# ASL2001.net
KiCad netlist of a schematic drawn in EAGLE
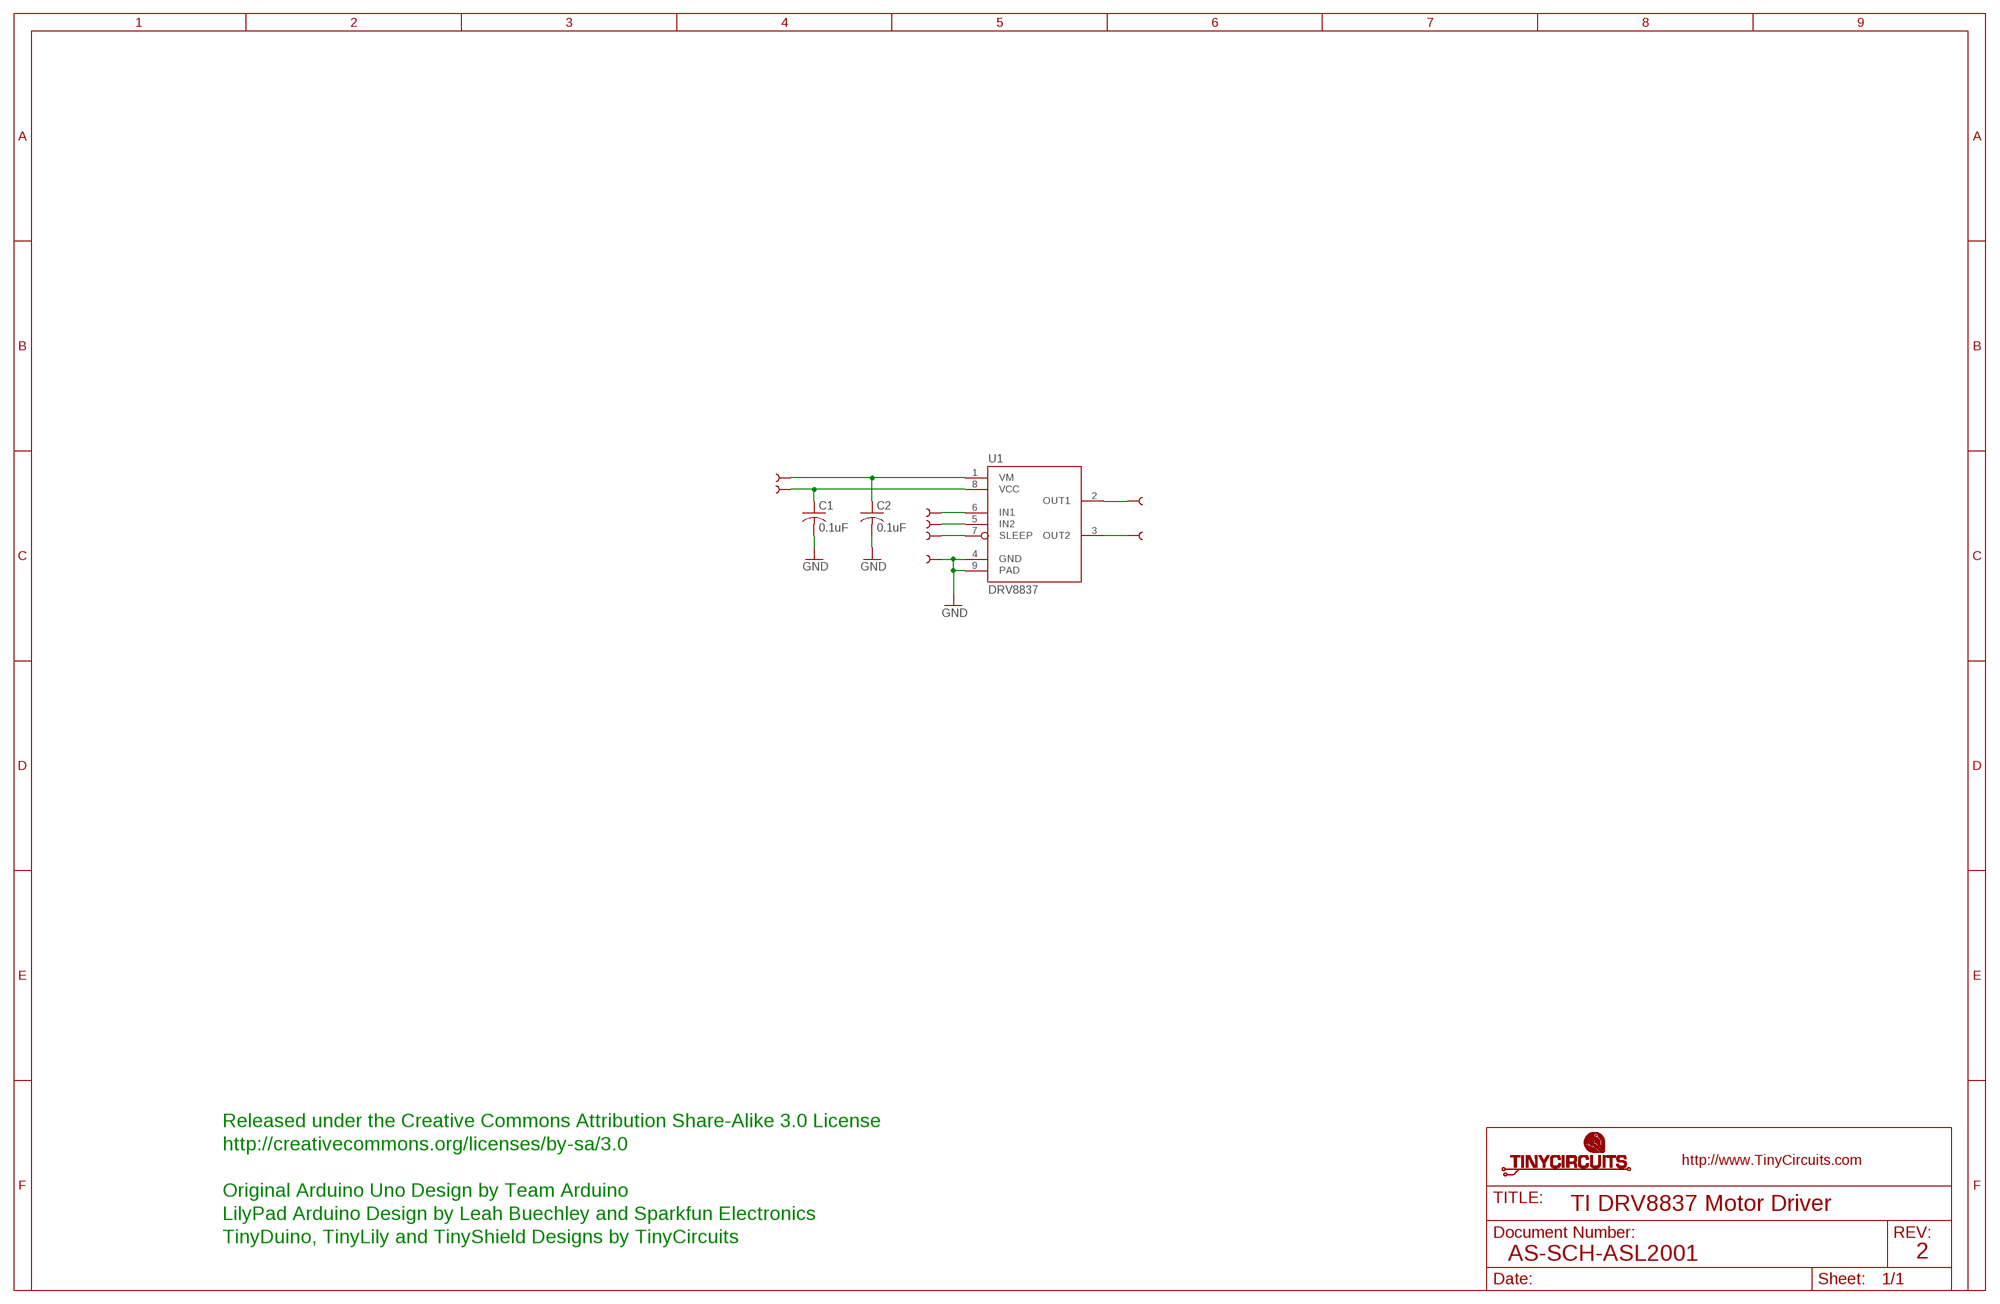
[diagram p0: schematic, sheet 1]

(export (version "E")
  (design (tool "Eeschema 10.0.6"))
  (components
    (comp (ref "C1")
      (value "0.1uF")
      (footprint "eagle-import:C0402")
      (fields (field (name "PARTNO") "AS-ITM-00008"))
      (libsource (lib "eagle-import") (part "AS-ITM-00008"))
    )
    (comp (ref "C2")
      (value "0.1uF")
      (footprint "eagle-import:C0402")
      (fields (field (name "PARTNO") "AS-ITM-00008"))
      (libsource (lib "eagle-import") (part "AS-ITM-00008"))
    )
    (comp (ref "U$2")
      (value "SEWTABTH_0402")
      (footprint "eagle-import:SEWTAP_TH_0402")
      (libsource (lib "eagle-import") (part "SEWTABTH_0402"))
    )
    (comp (ref "U$3")
      (value "SEWTABTH_0402")
      (footprint "eagle-import:SEWTAP_TH_0402")
      (libsource (lib "eagle-import") (part "SEWTABTH_0402"))
    )
    (comp (ref "U$4")
      (value "SEWTABTH_0402")
      (footprint "eagle-import:SEWTAP_TH_0402")
      (libsource (lib "eagle-import") (part "SEWTABTH_0402"))
    )
    (comp (ref "U$5")
      (value "SEWTABTH_0402")
      (footprint "eagle-import:SEWTAP_TH_0402")
      (libsource (lib "eagle-import") (part "SEWTABTH_0402"))
    )
    (comp (ref "U$8")
      (value "SEWTABTH_0402")
      (footprint "eagle-import:SEWTAP_TH_0402")
      (libsource (lib "eagle-import") (part "SEWTABTH_0402"))
    )
    (comp (ref "U$9")
      (value "SEWTABTH_0402")
      (footprint "eagle-import:SEWTAP_TH_0402")
      (libsource (lib "eagle-import") (part "SEWTABTH_0402"))
    )
    (comp (ref "U$10")
      (value "SEWTABTH_0402")
      (footprint "eagle-import:SEWTAP_TH_0402")
      (libsource (lib "eagle-import") (part "SEWTABTH_0402"))
    )
    (comp (ref "U$11")
      (value "SEWTABTH_0402")
      (footprint "eagle-import:SEWTAP_TH_0402")
      (libsource (lib "eagle-import") (part "SEWTABTH_0402"))
    )
    (comp (ref "U1")
      (value "DRV8837")
      (footprint "eagle-import:WSON-8")
      (fields (field (name "PARTNO") "AS-ITM-00042"))
      (libsource (lib "eagle-import") (part "AS-ITM-00042"))
    )
  )
  (nets
    (net (code "1") (name "GND") (class "Default")
      (node (ref "C1") (pin "2") (pinfunction "2_2") (pintype "passive"))
      (node (ref "C2") (pin "2") (pinfunction "2_2") (pintype "passive"))
      (node (ref "U$9") (pin "1") (pinfunction "1_1") (pintype "bidirectional"))
      (node (ref "U1") (pin "4") (pinfunction "GND_4") (pintype "power_in"))
      (node (ref "U1") (pin "9") (pinfunction "PAD_9") (pintype "power_in"))
    )
    (net (code "2") (name "Net-(U1-IN1)") (class "Default")
      (node (ref "U$4") (pin "1") (pinfunction "1_1") (pintype "bidirectional"))
      (node (ref "U1") (pin "6") (pinfunction "IN1_6") (pintype "power_in"))
    )
    (net (code "3") (name "Net-(U1-IN2)") (class "Default")
      (node (ref "U$5") (pin "1") (pinfunction "1_1") (pintype "bidirectional"))
      (node (ref "U1") (pin "5") (pinfunction "IN2_5") (pintype "power_in"))
    )
    (net (code "4") (name "Net-(U1-OUT1)") (class "Default")
      (node (ref "U$10") (pin "1") (pinfunction "1_1") (pintype "bidirectional"))
      (node (ref "U1") (pin "2") (pinfunction "OUT1_2") (pintype "bidirectional"))
    )
    (net (code "5") (name "Net-(U1-OUT2)") (class "Default")
      (node (ref "U$11") (pin "1") (pinfunction "1_1") (pintype "bidirectional"))
      (node (ref "U1") (pin "3") (pinfunction "OUT2_3") (pintype "bidirectional"))
    )
    (net (code "6") (name "Net-(U1-SLEEP)") (class "Default")
      (node (ref "U$8") (pin "1") (pinfunction "1_1") (pintype "bidirectional"))
      (node (ref "U1") (pin "7") (pinfunction "SLEEP_7") (pintype "bidirectional"))
    )
    (net (code "7") (name "Net-(U1-VCC)") (class "Default")
      (node (ref "C1") (pin "1") (pinfunction "1_1") (pintype "passive"))
      (node (ref "U$2") (pin "1") (pinfunction "1_1") (pintype "bidirectional"))
      (node (ref "U1") (pin "8") (pinfunction "VCC_8") (pintype "bidirectional"))
    )
    (net (code "8") (name "Net-(U1-VM)") (class "Default")
      (node (ref "C2") (pin "1") (pinfunction "1_1") (pintype "passive"))
      (node (ref "U$3") (pin "1") (pinfunction "1_1") (pintype "bidirectional"))
      (node (ref "U1") (pin "1") (pinfunction "VM_1") (pintype "bidirectional"))
    )
  )
)
